# Sensors.net
KiCad netlist of a schematic drawn in Altium Designer
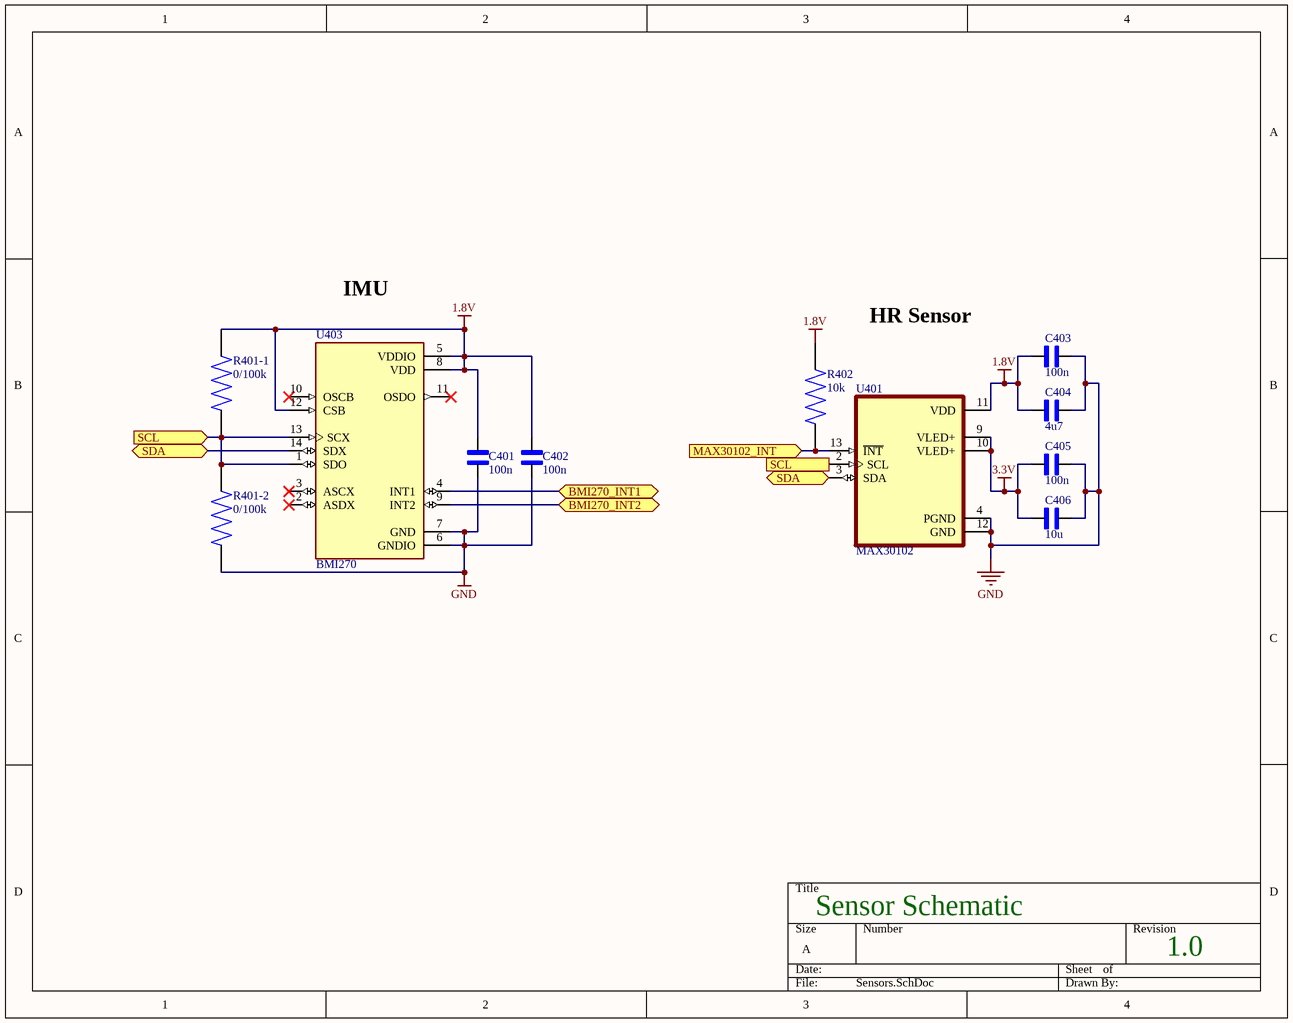
[diagram p0: Sensors.SchDoc]

(export (version "E")
  (design (tool "Eeschema 10.0.6"))
  (components
    (comp (ref "C401") (value "100n") (footprint "0402c") (libsource (lib "UbiWatch_SchLib") (part "0402c")))
    (comp (ref "C402") (value "100n") (footprint "0402c") (libsource (lib "UbiWatch_SchLib") (part "0402c")))
    (comp (ref "C403") (value "100n") (footprint "0402c") (libsource (lib "") (part "0402c_1")))
    (comp (ref "C404") (value "4u7") (footprint "0603c") (libsource (lib "UbiWatch_SchLib") (part "0603c")))
    (comp (ref "C405") (value "100n") (footprint "0402c") (libsource (lib "") (part "0402c_1")))
    (comp (ref "C406") (value "10u") (footprint "0603c") (libsource (lib "UbiWatch_SchLib") (part "0603c")))
    (comp (ref "R401-1")
      (value "0/100k")
      (footprint "0402r")
      (libsource (lib "UbiWatch_SchLib") (part "0402r"))
    )
    (comp (ref "R401-2")
      (value "0/100k")
      (footprint "0402r")
      (libsource (lib "UbiWatch_SchLib") (part "0402r"))
    )
    (comp (ref "R402") (value "10k") (footprint "0402r") (libsource (lib "UbiWatch_SchLib") (part "0402r")))
    (comp (ref "U401")
      (value "MAX30102")
      (footprint "MAX30102")
      (libsource (lib "JWatch_SchLib") (part "MAX30102"))
    )
    (comp (ref "U403")
      (value "BMI270")
      (footprint "BMI270")
      (libsource (lib "JWatch_SchLib") (part "BMI270"))
    )
  )
  (nets
    (net (code "1") (name "/BMI270_INT1") (class "Default")
      (node (ref "U403") (pin "4") (pinfunction "INT1_4") (pintype "bidirectional"))
    )
    (net (code "2") (name "/BMI270_INT2") (class "Default")
      (node (ref "U403") (pin "9") (pinfunction "INT2_9") (pintype "bidirectional"))
    )
    (net (code "3") (name "/MAX30102_INT") (class "Default")
      (node (ref "R402") (pin "1") (pinfunction "1_1") (pintype "passive"))
      (node (ref "U401") (pin "13") (pinfunction "~{INT}_13") (pintype "input"))
    )
    (net (code "4") (name "/SCL") (class "Default")
      (node (ref "R401-1") (pin "1") (pinfunction "1_1") (pintype "passive"))
      (node (ref "R401-2") (pin "2") (pinfunction "2_2") (pintype "passive"))
      (node (ref "U401") (pin "2") (pinfunction "SCL_2") (pintype "input"))
      (node (ref "U403") (pin "1") (pinfunction "SDO_1") (pintype "bidirectional"))
      (node (ref "U403") (pin "13") (pinfunction "SCX_13") (pintype "input"))
    )
    (net (code "5") (name "/SDA") (class "Default")
      (node (ref "U401") (pin "3") (pinfunction "SDA_3") (pintype "bidirectional"))
      (node (ref "U403") (pin "14") (pinfunction "SDX_14") (pintype "bidirectional"))
    )
    (net (code "6") (name "1.8V") (class "Default")
      (node (ref "C401") (pin "2") (pinfunction "2_2") (pintype "passive"))
      (node (ref "C402") (pin "2") (pinfunction "2_2") (pintype "passive"))
      (node (ref "C403") (pin "2") (pinfunction "2_2") (pintype "passive"))
      (node (ref "C404") (pin "2") (pinfunction "2_2") (pintype "passive"))
      (node (ref "R401-1") (pin "2") (pinfunction "2_2") (pintype "passive"))
      (node (ref "R402") (pin "2") (pinfunction "2_2") (pintype "passive"))
      (node (ref "U401") (pin "11") (pinfunction "VDD_11") (pintype "power_in"))
      (node (ref "U403") (pin "12") (pinfunction "CSB_12") (pintype "input"))
      (node (ref "U403") (pin "5") (pinfunction "VDDIO_5") (pintype "power_in"))
      (node (ref "U403") (pin "8") (pinfunction "VDD_8") (pintype "power_in"))
    )
    (net (code "7") (name "3.3V") (class "Default")
      (node (ref "C405") (pin "2") (pinfunction "2_2") (pintype "passive"))
      (node (ref "C406") (pin "2") (pinfunction "2_2") (pintype "passive"))
      (node (ref "U401") (pin "10") (pinfunction "VLED+_10") (pintype "power_in"))
      (node (ref "U401") (pin "9") (pinfunction "VLED+_9") (pintype "power_in"))
    )
    (net (code "8") (name "GND") (class "Default")
      (node (ref "C401") (pin "1") (pinfunction "1_1") (pintype "passive"))
      (node (ref "C402") (pin "1") (pinfunction "1_1") (pintype "passive"))
      (node (ref "C403") (pin "1") (pinfunction "1_1") (pintype "passive"))
      (node (ref "C404") (pin "1") (pinfunction "1_1") (pintype "passive"))
      (node (ref "C405") (pin "1") (pinfunction "1_1") (pintype "passive"))
      (node (ref "C406") (pin "1") (pinfunction "1_1") (pintype "passive"))
      (node (ref "R401-2") (pin "1") (pinfunction "1_1") (pintype "passive"))
      (node (ref "U401") (pin "12") (pinfunction "GND_12") (pintype "power_in"))
      (node (ref "U401") (pin "4") (pinfunction "PGND_4") (pintype "power_in"))
      (node (ref "U403") (pin "6") (pinfunction "GNDIO_6") (pintype "power_in"))
      (node (ref "U403") (pin "7") (pinfunction "GND_7") (pintype "power_in"))
    )
    (net (code "9") (name "unconnected-(U403-ASCX-Pad3)") (class "Default")
      (node (ref "U403") (pin "3") (pinfunction "ASCX_3") (pintype "bidirectional+no_connect"))
    )
    (net (code "10") (name "unconnected-(U403-ASDX-Pad2)") (class "Default")
      (node (ref "U403") (pin "2") (pinfunction "ASDX_2") (pintype "bidirectional+no_connect"))
    )
    (net (code "11") (name "unconnected-(U403-OSCB-Pad10)") (class "Default")
      (node (ref "U403") (pin "10") (pinfunction "OSCB_10") (pintype "input+no_connect"))
    )
    (net (code "12") (name "unconnected-(U403-OSDO-Pad11)") (class "Default")
      (node (ref "U403") (pin "11") (pinfunction "OSDO_11") (pintype "output+no_connect"))
    )
  )
)
